# Charger_Relay_Board_rev1.net
KiCad netlist of a schematic drawn in EAGLE
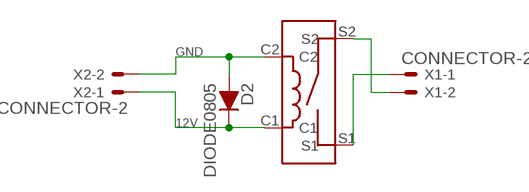
[diagram p0: schematic, sheet 1]

(export (version "E")
  (design (tool "Eeschema 10.0.6"))
  (components
    (comp (ref "D2")
      (value "DIODE0805")
      (footprint "eagle-import:0805_D")
      (libsource (lib "eagle-import") (part "DIODE0805"))
    )
    (comp (ref "U$1")
      (value "KT12-1A-40L-THT")
      (footprint "eagle-import:KT12-1A-40L-THT")
      (libsource (lib "eagle-import") (part "KT12-1A-40L-THT"))
    )
    (comp (ref "X1")
      (value "CONNECTOR-2")
      (footprint "eagle-import:MINIFIT_5566-2")
      (libsource (lib "eagle-import") (part "CONNECTOR-2"))
    )
    (comp (ref "X2")
      (value "CONNECTOR-2")
      (footprint "eagle-import:MINIFIT_5566-2")
      (libsource (lib "eagle-import") (part "CONNECTOR-2"))
    )
  )
  (nets
    (net (code "1") (name "/12V") (class "Default")
      (node (ref "D2") (pin "C") (pinfunction "C_C") (pintype "passive"))
      (node (ref "U$1") (pin "C1") (pinfunction "C1_C1") (pintype "bidirectional"))
      (node (ref "X2") (pin "1") (pinfunction "S_1") (pintype "passive"))
    )
    (net (code "2") (name "/GND") (class "Default")
      (node (ref "D2") (pin "A") (pinfunction "A_A") (pintype "passive"))
      (node (ref "U$1") (pin "C2") (pinfunction "C2_C2") (pintype "bidirectional"))
      (node (ref "X2") (pin "2") (pinfunction "S_2") (pintype "passive"))
    )
    (net (code "3") (name "Net-(X1A-S)") (class "Default")
      (node (ref "U$1") (pin "S1") (pinfunction "S1_S1") (pintype "bidirectional"))
      (node (ref "X1") (pin "1") (pinfunction "S_1") (pintype "passive"))
    )
    (net (code "4") (name "Net-(X1B-S)") (class "Default")
      (node (ref "U$1") (pin "S2") (pinfunction "S2_S2") (pintype "bidirectional"))
      (node (ref "X1") (pin "2") (pinfunction "S_2") (pintype "passive"))
    )
  )
)
